# RGB_Blinker.net
KiCad netlist of a schematic drawn in EAGLE
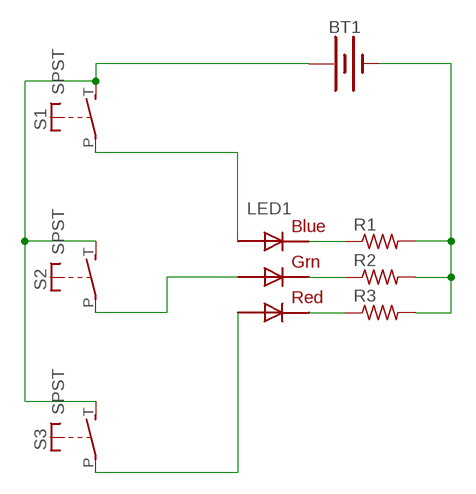
[diagram p0: schematic, sheet 1]

(export (version "E")
  (design (tool "Eeschema 10.0.6"))
  (components
    (comp (ref "BT1")
      (value "BATTERY-20MM_SMD")
      (footprint "eagle-import:BATTCON_20MM")
      (libsource (lib "eagle-import") (part "BATTERY-20MM_SMD"))
    )
    (comp (ref "LED1")
      (value "RGBLED5050")
      (footprint "eagle-import:RGBLED5050")
      (libsource (lib "eagle-import") (part "RGBLED5050"))
    )
    (comp (ref "R1")
      (value "R-US_M2012")
      (footprint "eagle-import:M2012")
      (libsource (lib "eagle-import") (part "R-US_M2012"))
    )
    (comp (ref "R2")
      (value "R-US_M2012")
      (footprint "eagle-import:M2012")
      (libsource (lib "eagle-import") (part "R-US_M2012"))
    )
    (comp (ref "R3")
      (value "R-US_M2012")
      (footprint "eagle-import:M2012")
      (libsource (lib "eagle-import") (part "R-US_M2012"))
    )
    (comp (ref "S1")
      (value "SPST")
      (footprint "eagle-import:JUDCOSPST")
      (libsource (lib "eagle-import") (part "SPST"))
    )
    (comp (ref "S2")
      (value "SPST")
      (footprint "eagle-import:JUDCOSPST")
      (libsource (lib "eagle-import") (part "SPST"))
    )
    (comp (ref "S3")
      (value "SPST")
      (footprint "eagle-import:JUDCOSPST")
      (libsource (lib "eagle-import") (part "SPST"))
    )
  )
  (nets
    (net (code "1") (name "Net-(BT1-+)") (class "Default")
      (node (ref "BT1") (pin "1") (pinfunction "+_1") (pintype "power_in"))
      (node (ref "S1") (pin "T") (pinfunction "S_T") (pintype "passive"))
      (node (ref "S2") (pin "T") (pinfunction "S_T") (pintype "passive"))
      (node (ref "S3") (pin "T") (pinfunction "S_T") (pintype "passive"))
    )
    (net (code "2") (name "Net-(BT1--)") (class "Default")
      (node (ref "BT1") (pin "2") (pinfunction "-_2") (pintype "power_in"))
      (node (ref "R1") (pin "2") (pinfunction "2_2") (pintype "passive"))
      (node (ref "R2") (pin "2") (pinfunction "2_2") (pintype "passive"))
      (node (ref "R3") (pin "2") (pinfunction "2_2") (pintype "passive"))
    )
    (net (code "3") (name "Net-(LED1-BLUE_A)") (class "Default")
      (node (ref "LED1") (pin "3") (pinfunction "BLUE_A_3") (pintype "bidirectional"))
      (node (ref "S1") (pin "P") (pinfunction "P_P") (pintype "passive"))
    )
    (net (code "4") (name "Net-(LED1-BLUE_C)") (class "Default")
      (node (ref "LED1") (pin "4") (pinfunction "BLUE_C_4") (pintype "bidirectional"))
      (node (ref "R1") (pin "1") (pinfunction "1_1") (pintype "passive"))
    )
    (net (code "5") (name "Net-(LED1-GREEN_A)") (class "Default")
      (node (ref "LED1") (pin "1") (pinfunction "GREEN_A_1") (pintype "bidirectional"))
      (node (ref "S2") (pin "P") (pinfunction "P_P") (pintype "passive"))
    )
    (net (code "6") (name "Net-(LED1-GREEN_C)") (class "Default")
      (node (ref "LED1") (pin "6") (pinfunction "GREEN_C_6") (pintype "bidirectional"))
      (node (ref "R2") (pin "1") (pinfunction "1_1") (pintype "passive"))
    )
    (net (code "7") (name "Net-(LED1-RED_A)") (class "Default")
      (node (ref "LED1") (pin "2") (pinfunction "RED_A_2") (pintype "bidirectional"))
      (node (ref "S3") (pin "P") (pinfunction "P_P") (pintype "passive"))
    )
    (net (code "8") (name "Net-(LED1-RED_C)") (class "Default")
      (node (ref "LED1") (pin "5") (pinfunction "RED_C_5") (pintype "bidirectional"))
      (node (ref "R3") (pin "1") (pinfunction "1_1") (pintype "passive"))
    )
  )
)
